# 2_SLOT_PCB.net
KiCad netlist of a schematic drawn in Altium Designer
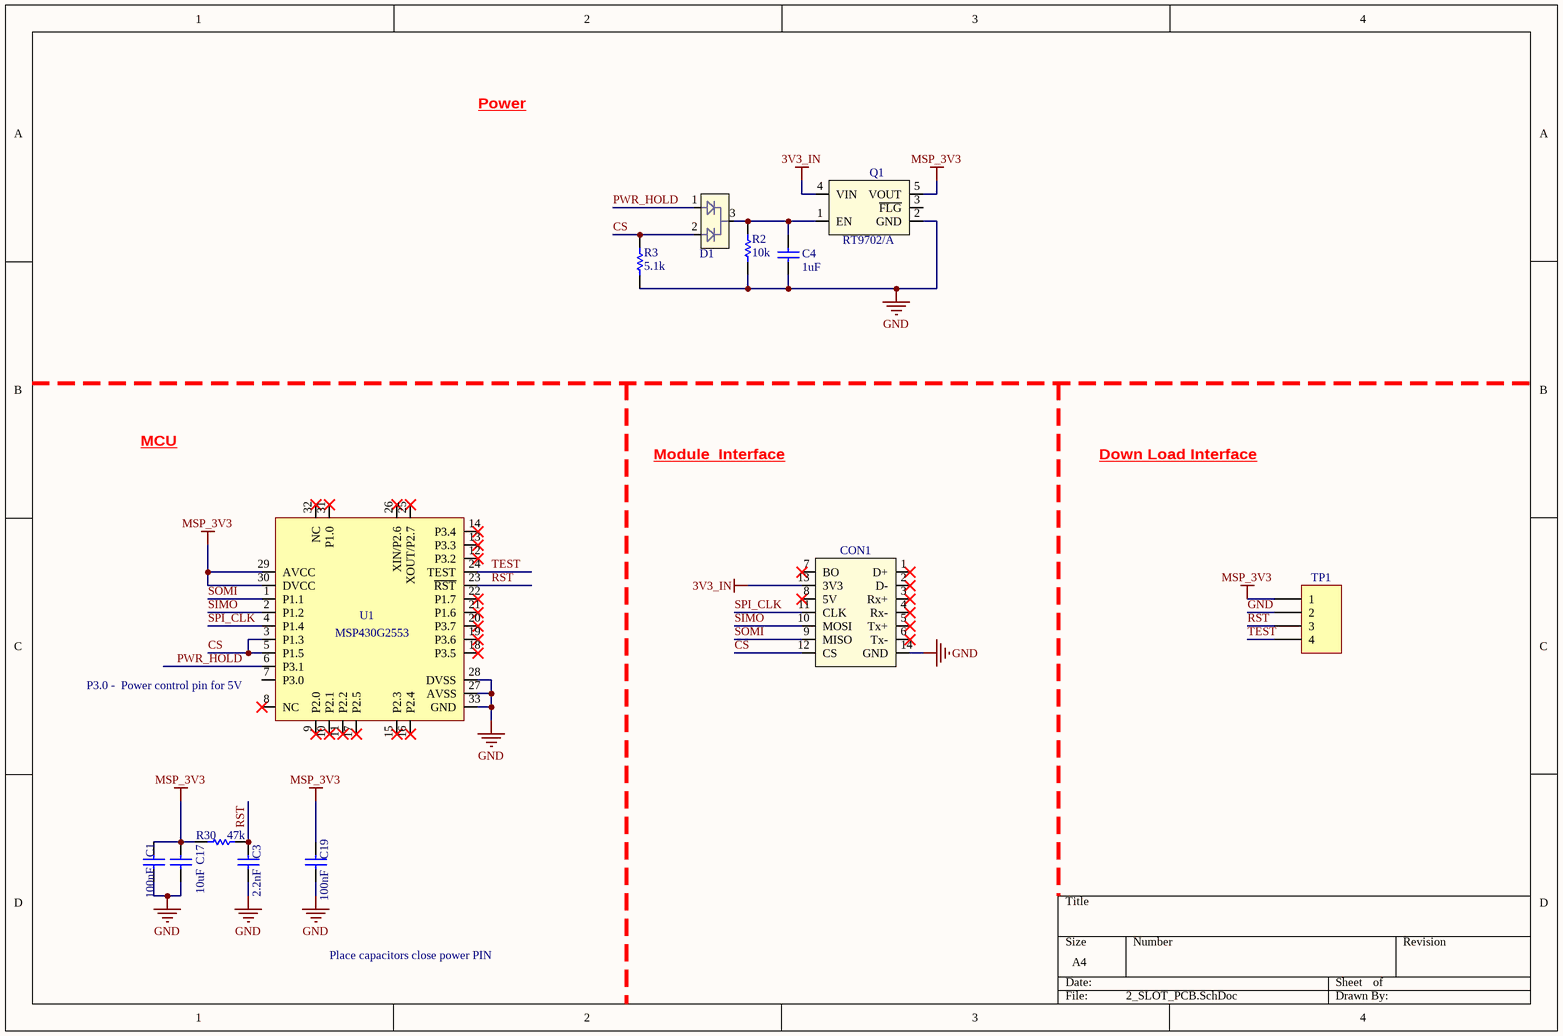
[diagram p0: 2_SLOT_PCB.SchDoc]

(export (version "E")
  (design (tool "Eeschema 10.0.6"))
  (components
    (comp (ref "C1")
      (value "100nF")
      (footprint "0402")
      (description "Capacitor")
      (fields (field (name "Comment") "Cap") (field (name "PUBLISHER") "Altium Limited"))
      (libsource (lib "Miscellaneous Devices") (part "Cap"))
    )
    (comp (ref "C3")
      (value "2.2nF")
      (footprint "0402")
      (description "Capacitor")
      (fields (field (name "Comment") "Cap") (field (name "PUBLISHER") "Altium Limited"))
      (libsource (lib "Miscellaneous Devices") (part "Cap"))
    )
    (comp (ref "C4")
      (value "1uF")
      (footprint "0402")
      (description "Capacitor")
      (fields (field (name "Comment") "Cap") (field (name "PUBLISHER") "Altium Limited"))
      (libsource (lib "Miscellaneous Devices") (part "Cap"))
    )
    (comp (ref "C17")
      (value "10uF")
      (footprint "0603")
      (description "Capacitor")
      (fields (field (name "Comment") "Cap") (field (name "PUBLISHER") "Altium Limited"))
      (libsource (lib "Miscellaneous Devices") (part "Cap"))
    )
    (comp (ref "C19")
      (value "100nF")
      (footprint "0402")
      (description "Capacitor")
      (fields (field (name "Comment") "Cap") (field (name "PUBLISHER") "Altium Limited"))
      (libsource (lib "Miscellaneous Devices") (part "Cap"))
    )
    (comp (ref "CON1")
      (value "~")
      (footprint "edge-connector-0.8*1.0")
      (description "Module interface")
      (libsource (lib "Connector") (part "NP_EdgeConnector-2*7"))
    )
    (comp (ref "D1")
      (value "Dual Diode (common cath)")
      (footprint "SOT-523")
      (description "BAS40-05T")
      (fields (field (name "MANUFACTURER") "DIODES") (field (name "PART NUMBER") "BAS40-05T-7-F"))
      (libsource (lib "Discrete") (part "Dual Diode (common cath)"))
    )
    (comp (ref "Q1")
      (value "RT9702/A")
      (footprint "SOT-23-5")
      (description "RICHTEK RT9702/A")
      (fields (field (name "MANUFACTURER") "RICHTEK") (field (name "PART NUMBER") "RT9702/A GB"))
      (libsource (lib "Discrete") (part "RT9702/A"))
    )
    (comp (ref "R2")
      (value "10k")
      (footprint "0402")
      (description "Resistor")
      (fields (field (name "Comment") "Res1") (field (name "PUBLISHER") "Altium Limited"))
      (libsource (lib "Miscellaneous Devices") (part "Res1"))
    )
    (comp (ref "R3")
      (value "5.1k")
      (footprint "0402")
      (description "Resistor")
      (fields (field (name "Comment") "Res1") (field (name "PUBLISHER") "Altium Limited"))
      (libsource (lib "Miscellaneous Devices") (part "Res1"))
    )
    (comp (ref "R30")
      (value "47k")
      (footprint "0402")
      (description "Resistor")
      (fields (field (name "Comment") "Res1") (field (name "PUBLISHER") "Altium Limited"))
      (libsource (lib "Miscellaneous Devices") (part "Res1"))
    )
    (comp (ref "TP1")
      (value "~")
      (footprint "header 4x1 30*30-55mil")
      (description "Down Load Interface")
      (fields (field (name "PUBLISHER") "Altium Limited"))
      (libsource (lib "Miscellaneous Connectors") (part "Header 4"))
    )
    (comp (ref "U1")
      (value "MSP430G2553")
      (footprint "QFN-32-5x5")
      (fields (field (name "MANUFACTURER") "TI") (field (name "PART NUMBER") "MSP430G2353IRHB32R"))
      (libsource (lib "IC") (part "MSP430G2553"))
    )
  )
  (nets
    (net (code "1") (name "/CS") (class "Default")
      (node (ref "CON1") (pin "12") (pinfunction "CS_12") (pintype "passive"))
      (node (ref "D1") (pin "2") (pinfunction "2_2") (pintype "passive"))
      (node (ref "R3") (pin "1") (pinfunction "1_1") (pintype "passive"))
      (node (ref "U1") (pin "3") (pinfunction "P1.3_3") (pintype "passive"))
      (node (ref "U1") (pin "5") (pinfunction "P1.5_5") (pintype "passive"))
    )
    (net (code "2") (name "/PWR_HOLD") (class "Default")
      (node (ref "D1") (pin "1") (pinfunction "1_1") (pintype "passive"))
      (node (ref "U1") (pin "6") (pinfunction "P3.1_6") (pintype "passive"))
    )
    (net (code "3") (name "/RST") (class "Default")
      (node (ref "C3") (pin "2") (pinfunction "2_2") (pintype "passive"))
      (node (ref "R30") (pin "1") (pinfunction "1_1") (pintype "passive"))
      (node (ref "TP1") (pin "3") (pinfunction "3_3") (pintype "passive"))
      (node (ref "U1") (pin "23") (pinfunction "~{RST}_23") (pintype "passive"))
    )
    (net (code "4") (name "/SIMO") (class "Default")
      (node (ref "CON1") (pin "10") (pinfunction "MOSI_10") (pintype "passive"))
      (node (ref "U1") (pin "2") (pinfunction "P1.2_2") (pintype "passive"))
    )
    (net (code "5") (name "/SOMI") (class "Default")
      (node (ref "CON1") (pin "9") (pinfunction "MISO_9") (pintype "passive"))
      (node (ref "U1") (pin "1") (pinfunction "P1.1_1") (pintype "passive"))
    )
    (net (code "6") (name "/SPI_CLK") (class "Default")
      (node (ref "CON1") (pin "11") (pinfunction "CLK_11") (pintype "passive"))
      (node (ref "U1") (pin "4") (pinfunction "P1.4_4") (pintype "passive"))
    )
    (net (code "7") (name "/TEST") (class "Default")
      (node (ref "TP1") (pin "4") (pinfunction "4_4") (pintype "passive"))
      (node (ref "U1") (pin "24") (pinfunction "TEST_24") (pintype "passive"))
    )
    (net (code "8") (name "3V3_IN") (class "Default")
      (node (ref "CON1") (pin "13") (pinfunction "3V3_13") (pintype "passive"))
      (node (ref "Q1") (pin "4") (pinfunction "VIN_4") (pintype "passive"))
    )
    (net (code "9") (name "GND") (class "Default")
      (node (ref "C1") (pin "1") (pinfunction "1_1") (pintype "passive"))
      (node (ref "C17") (pin "1") (pinfunction "1_1") (pintype "passive"))
      (node (ref "C19") (pin "1") (pinfunction "1_1") (pintype "passive"))
      (node (ref "C3") (pin "1") (pinfunction "1_1") (pintype "passive"))
      (node (ref "C4") (pin "1") (pinfunction "1_1") (pintype "passive"))
      (node (ref "CON1") (pin "14") (pinfunction "GND_14") (pintype "passive"))
      (node (ref "Q1") (pin "2") (pinfunction "GND_2") (pintype "passive"))
      (node (ref "R2") (pin "2") (pinfunction "2_2") (pintype "passive"))
      (node (ref "R3") (pin "2") (pinfunction "2_2") (pintype "passive"))
      (node (ref "TP1") (pin "2") (pinfunction "2_2") (pintype "passive"))
      (node (ref "U1") (pin "27") (pinfunction "AVSS_27") (pintype "passive"))
      (node (ref "U1") (pin "28") (pinfunction "DVSS_28") (pintype "passive"))
      (node (ref "U1") (pin "33") (pinfunction "GND_33") (pintype "passive"))
    )
    (net (code "10") (name "MSP_3V3") (class "Default")
      (node (ref "C1") (pin "2") (pinfunction "2_2") (pintype "passive"))
      (node (ref "C17") (pin "2") (pinfunction "2_2") (pintype "passive"))
      (node (ref "C19") (pin "2") (pinfunction "2_2") (pintype "passive"))
      (node (ref "Q1") (pin "5") (pinfunction "VOUT_5") (pintype "passive"))
      (node (ref "R30") (pin "2") (pinfunction "2_2") (pintype "passive"))
      (node (ref "TP1") (pin "1") (pinfunction "1_1") (pintype "passive"))
      (node (ref "U1") (pin "29") (pinfunction "AVCC_29") (pintype "passive"))
      (node (ref "U1") (pin "30") (pinfunction "DVCC_30") (pintype "passive"))
    )
    (net (code "11") (name "Net-(Q1-EN)") (class "Default")
      (node (ref "C4") (pin "2") (pinfunction "2_2") (pintype "passive"))
      (node (ref "D1") (pin "3") (pinfunction "3_3") (pintype "passive"))
      (node (ref "Q1") (pin "1") (pinfunction "EN_1") (pintype "passive"))
      (node (ref "R2") (pin "1") (pinfunction "1_1") (pintype "passive"))
    )
    (net (code "12") (name "unconnected-(CON1-5V-Pad8)") (class "Default")
      (node (ref "CON1") (pin "8") (pinfunction "5V_8") (pintype "passive+no_connect"))
    )
    (net (code "13") (name "unconnected-(CON1-BO-Pad7)") (class "Default")
      (node (ref "CON1") (pin "7") (pinfunction "BO_7") (pintype "passive+no_connect"))
    )
    (net (code "14") (name "unconnected-(CON1-D+-Pad1)") (class "Default")
      (node (ref "CON1") (pin "1") (pinfunction "D+_1") (pintype "passive+no_connect"))
    )
    (net (code "15") (name "unconnected-(CON1-D--Pad2)") (class "Default")
      (node (ref "CON1") (pin "2") (pinfunction "D-_2") (pintype "passive+no_connect"))
    )
    (net (code "16") (name "unconnected-(CON1-Rx+-Pad3)") (class "Default")
      (node (ref "CON1") (pin "3") (pinfunction "Rx+_3") (pintype "passive+no_connect"))
    )
    (net (code "17") (name "unconnected-(CON1-Rx--Pad4)") (class "Default")
      (node (ref "CON1") (pin "4") (pinfunction "Rx-_4") (pintype "passive+no_connect"))
    )
    (net (code "18") (name "unconnected-(CON1-Tx+-Pad5)") (class "Default")
      (node (ref "CON1") (pin "5") (pinfunction "Tx+_5") (pintype "passive+no_connect"))
    )
    (net (code "19") (name "unconnected-(CON1-Tx--Pad6)") (class "Default")
      (node (ref "CON1") (pin "6") (pinfunction "Tx-_6") (pintype "passive+no_connect"))
    )
    (net (code "20") (name "unconnected-(Q1-~{FLG}-Pad3)") (class "Default")
      (node (ref "Q1") (pin "3") (pinfunction "~{FLG}_3") (pintype "passive"))
    )
    (net (code "21") (name "unconnected-(U1-NC-Pad8)") (class "Default")
      (node (ref "U1") (pin "8") (pinfunction "NC_8") (pintype "passive+no_connect"))
    )
    (net (code "22") (name "unconnected-(U1-NC-Pad32)") (class "Default")
      (node (ref "U1") (pin "32") (pinfunction "NC_32") (pintype "passive+no_connect"))
    )
    (net (code "23") (name "unconnected-(U1-P1.0-Pad31)") (class "Default")
      (node (ref "U1") (pin "31") (pinfunction "P1.0_31") (pintype "passive+no_connect"))
    )
    (net (code "24") (name "unconnected-(U1-P1.6-Pad21)") (class "Default")
      (node (ref "U1") (pin "21") (pinfunction "P1.6_21") (pintype "passive+no_connect"))
    )
    (net (code "25") (name "unconnected-(U1-P1.7-Pad22)") (class "Default")
      (node (ref "U1") (pin "22") (pinfunction "P1.7_22") (pintype "passive+no_connect"))
    )
    (net (code "26") (name "unconnected-(U1-P2.0-Pad9)") (class "Default")
      (node (ref "U1") (pin "9") (pinfunction "P2.0_9") (pintype "passive+no_connect"))
    )
    (net (code "27") (name "unconnected-(U1-P2.1-Pad10)") (class "Default")
      (node (ref "U1") (pin "10") (pinfunction "P2.1_10") (pintype "passive+no_connect"))
    )
    (net (code "28") (name "unconnected-(U1-P2.2-Pad11)") (class "Default")
      (node (ref "U1") (pin "11") (pinfunction "P2.2_11") (pintype "passive+no_connect"))
    )
    (net (code "29") (name "unconnected-(U1-P2.3-Pad15)") (class "Default")
      (node (ref "U1") (pin "15") (pinfunction "P2.3_15") (pintype "passive+no_connect"))
    )
    (net (code "30") (name "unconnected-(U1-P2.4-Pad16)") (class "Default")
      (node (ref "U1") (pin "16") (pinfunction "P2.4_16") (pintype "passive+no_connect"))
    )
    (net (code "31") (name "unconnected-(U1-P2.5-Pad17)") (class "Default")
      (node (ref "U1") (pin "17") (pinfunction "P2.5_17") (pintype "passive+no_connect"))
    )
    (net (code "32") (name "unconnected-(U1-P3.0-Pad7)") (class "Default")
      (node (ref "U1") (pin "7") (pinfunction "P3.0_7") (pintype "passive"))
    )
    (net (code "33") (name "unconnected-(U1-P3.2-Pad12)") (class "Default")
      (node (ref "U1") (pin "12") (pinfunction "P3.2_12") (pintype "passive+no_connect"))
    )
    (net (code "34") (name "unconnected-(U1-P3.3-Pad13)") (class "Default")
      (node (ref "U1") (pin "13") (pinfunction "P3.3_13") (pintype "passive+no_connect"))
    )
    (net (code "35") (name "unconnected-(U1-P3.4-Pad14)") (class "Default")
      (node (ref "U1") (pin "14") (pinfunction "P3.4_14") (pintype "passive+no_connect"))
    )
    (net (code "36") (name "unconnected-(U1-P3.5-Pad18)") (class "Default")
      (node (ref "U1") (pin "18") (pinfunction "P3.5_18") (pintype "passive+no_connect"))
    )
    (net (code "37") (name "unconnected-(U1-P3.6-Pad19)") (class "Default")
      (node (ref "U1") (pin "19") (pinfunction "P3.6_19") (pintype "passive+no_connect"))
    )
    (net (code "38") (name "unconnected-(U1-P3.7-Pad20)") (class "Default")
      (node (ref "U1") (pin "20") (pinfunction "P3.7_20") (pintype "passive+no_connect"))
    )
    (net (code "39") (name "unconnected-(U1-XIN{slash}P2.6-Pad26)") (class "Default")
      (node (ref "U1") (pin "26") (pinfunction "XIN/P2.6_26") (pintype "passive+no_connect"))
    )
    (net (code "40") (name "unconnected-(U1-XOUT{slash}P2.7-Pad25)") (class "Default")
      (node (ref "U1") (pin "25") (pinfunction "XOUT/P2.7_25") (pintype "passive+no_connect"))
    )
  )
)
